# Blue_Pill_Base_Shield.net
KiCad netlist of a schematic drawn in EAGLE
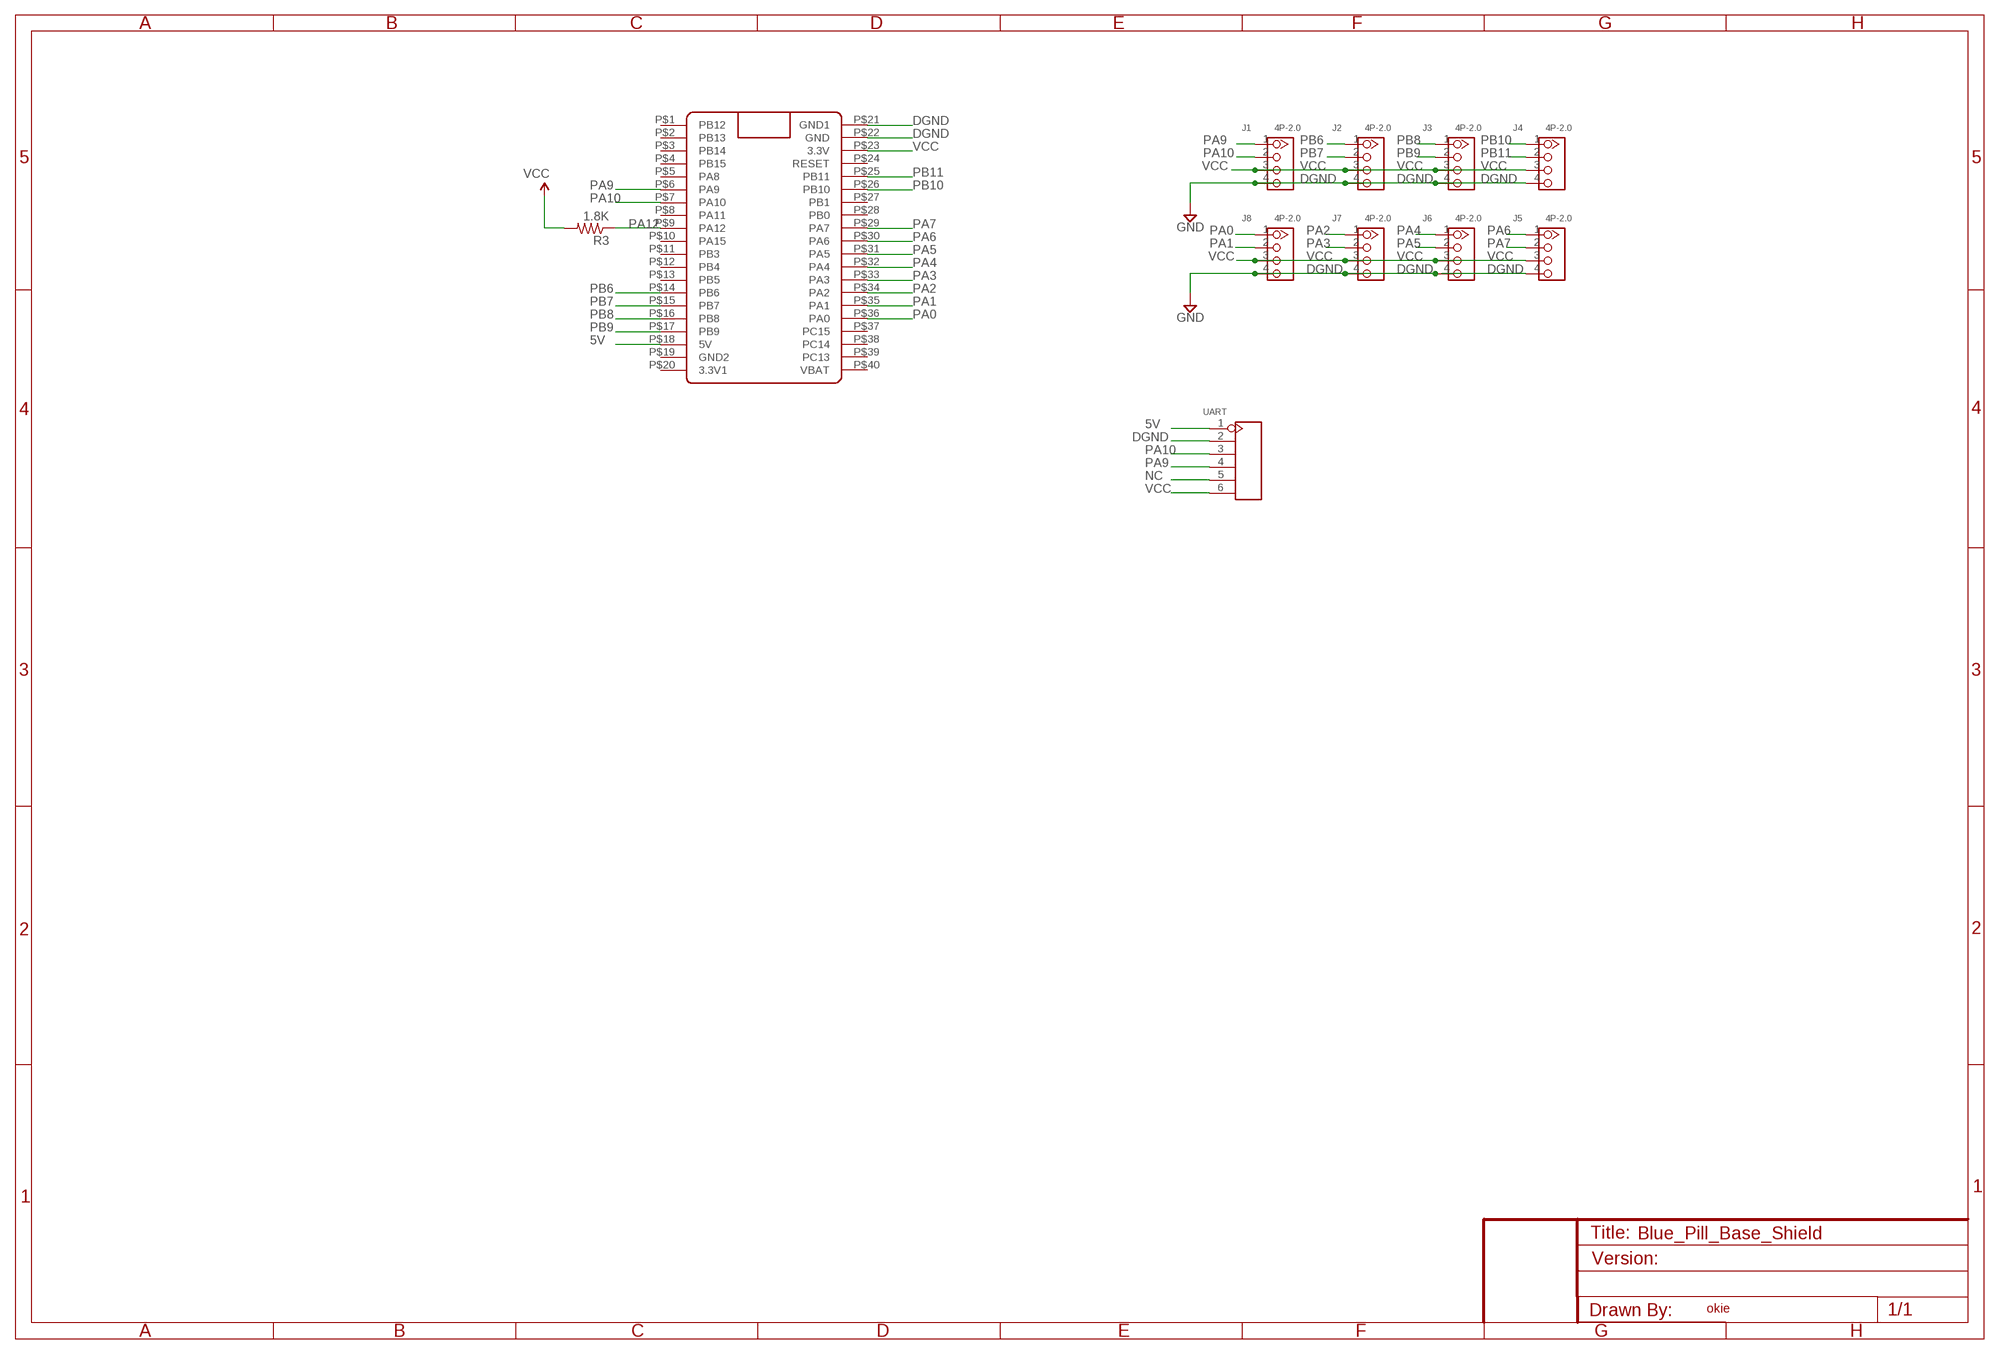
[diagram p0: schematic, sheet 1]

(export (version "E")
  (design (tool "Eeschema 10.0.6"))
  (components
    (comp (ref "J1")
      (value "4P-2.0")
      (footprint "eagle-import:HW4-2.0")
      (libsource (lib "eagle-import") (part "GROVE-CONNECTOR-DIP(4P-2.0)"))
    )
    (comp (ref "J2")
      (value "4P-2.0")
      (footprint "eagle-import:HW4-2.0")
      (libsource (lib "eagle-import") (part "GROVE-CONNECTOR-DIP(4P-2.0)"))
    )
    (comp (ref "J3")
      (value "4P-2.0")
      (footprint "eagle-import:HW4-2.0")
      (libsource (lib "eagle-import") (part "GROVE-CONNECTOR-DIP(4P-2.0)"))
    )
    (comp (ref "J4")
      (value "4P-2.0")
      (footprint "eagle-import:HW4-2.0")
      (libsource (lib "eagle-import") (part "GROVE-CONNECTOR-DIP(4P-2.0)"))
    )
    (comp (ref "J5")
      (value "4P-2.0")
      (footprint "eagle-import:HW4-2.0")
      (libsource (lib "eagle-import") (part "GROVE-CONNECTOR-DIP(4P-2.0)"))
    )
    (comp (ref "J6")
      (value "4P-2.0")
      (footprint "eagle-import:HW4-2.0")
      (libsource (lib "eagle-import") (part "GROVE-CONNECTOR-DIP(4P-2.0)"))
    )
    (comp (ref "J7")
      (value "4P-2.0")
      (footprint "eagle-import:HW4-2.0")
      (libsource (lib "eagle-import") (part "GROVE-CONNECTOR-DIP(4P-2.0)"))
    )
    (comp (ref "J8")
      (value "4P-2.0")
      (footprint "eagle-import:HW4-2.0")
      (libsource (lib "eagle-import") (part "GROVE-CONNECTOR-DIP(4P-2.0)"))
    )
    (comp (ref "R3")
      (value "1.8K")
      (footprint "eagle-import:0603")
      (libsource (lib "eagle-import") (part "RESISTOR0603"))
    )
    (comp (ref "U$5")
      (value "BLUE_PILL")
      (footprint "eagle-import:BLUE_PILL")
      (libsource (lib "eagle-import") (part "BLUE_PILL"))
    )
    (comp (ref "UART")
      (value "YELLOW-6P-2.54")
      (footprint "eagle-import:H6-2.54")
      (fields (field (name "MPN") "F185-1106A1BSYA3"))
      (libsource (lib "eagle-import") (part "DIP-YELLOW-FEMALE-HEADER-VERT(6P-2.54)"))
    )
  )
  (nets
    (net (code "1") (name "/5V") (class "Default")
      (node (ref "U$5") (pin "P$18") (pinfunction "5V_P$18") (pintype "bidirectional"))
      (node (ref "UART") (pin "1") (pinfunction "1_1") (pintype "bidirectional"))
    )
    (net (code "2") (name "/NC") (class "Default")
      (node (ref "UART") (pin "5") (pinfunction "5_5") (pintype "bidirectional"))
    )
    (net (code "3") (name "/PA0") (class "Default")
      (node (ref "J8") (pin "1") (pinfunction "1_1") (pintype "bidirectional"))
      (node (ref "U$5") (pin "P$36") (pinfunction "PA0_P$36") (pintype "bidirectional"))
    )
    (net (code "4") (name "/PA1") (class "Default")
      (node (ref "J8") (pin "2") (pinfunction "2_2") (pintype "bidirectional"))
      (node (ref "U$5") (pin "P$35") (pinfunction "PA1_P$35") (pintype "bidirectional"))
    )
    (net (code "5") (name "/PA2") (class "Default")
      (node (ref "J7") (pin "1") (pinfunction "1_1") (pintype "bidirectional"))
      (node (ref "U$5") (pin "P$34") (pinfunction "PA2_P$34") (pintype "bidirectional"))
    )
    (net (code "6") (name "/PA3") (class "Default")
      (node (ref "J7") (pin "2") (pinfunction "2_2") (pintype "bidirectional"))
      (node (ref "U$5") (pin "P$33") (pinfunction "PA3_P$33") (pintype "bidirectional"))
    )
    (net (code "7") (name "/PA4") (class "Default")
      (node (ref "J6") (pin "1") (pinfunction "1_1") (pintype "bidirectional"))
      (node (ref "U$5") (pin "P$32") (pinfunction "PA4_P$32") (pintype "bidirectional"))
    )
    (net (code "8") (name "/PA5") (class "Default")
      (node (ref "J6") (pin "2") (pinfunction "2_2") (pintype "bidirectional"))
      (node (ref "U$5") (pin "P$31") (pinfunction "PA5_P$31") (pintype "bidirectional"))
    )
    (net (code "9") (name "/PA6") (class "Default")
      (node (ref "J5") (pin "1") (pinfunction "1_1") (pintype "bidirectional"))
      (node (ref "U$5") (pin "P$30") (pinfunction "PA6_P$30") (pintype "bidirectional"))
    )
    (net (code "10") (name "/PA7") (class "Default")
      (node (ref "J5") (pin "2") (pinfunction "2_2") (pintype "bidirectional"))
      (node (ref "U$5") (pin "P$29") (pinfunction "PA7_P$29") (pintype "bidirectional"))
    )
    (net (code "11") (name "/PA9") (class "Default")
      (node (ref "J1") (pin "1") (pinfunction "1_1") (pintype "bidirectional"))
      (node (ref "U$5") (pin "P$6") (pinfunction "PA9_P$6") (pintype "bidirectional"))
      (node (ref "UART") (pin "4") (pinfunction "4_4") (pintype "bidirectional"))
    )
    (net (code "12") (name "/PA10") (class "Default")
      (node (ref "J1") (pin "2") (pinfunction "2_2") (pintype "bidirectional"))
      (node (ref "U$5") (pin "P$7") (pinfunction "PA10_P$7") (pintype "bidirectional"))
      (node (ref "UART") (pin "3") (pinfunction "3_3") (pintype "bidirectional"))
    )
    (net (code "13") (name "/PA12") (class "Default")
      (node (ref "R3") (pin "1") (pinfunction "1_1") (pintype "passive"))
      (node (ref "U$5") (pin "P$9") (pinfunction "PA12_P$9") (pintype "bidirectional"))
    )
    (net (code "14") (name "/PB6") (class "Default")
      (node (ref "J2") (pin "1") (pinfunction "1_1") (pintype "bidirectional"))
      (node (ref "U$5") (pin "P$14") (pinfunction "PB6_P$14") (pintype "bidirectional"))
    )
    (net (code "15") (name "/PB7") (class "Default")
      (node (ref "J2") (pin "2") (pinfunction "2_2") (pintype "bidirectional"))
      (node (ref "U$5") (pin "P$15") (pinfunction "PB7_P$15") (pintype "bidirectional"))
    )
    (net (code "16") (name "/PB8") (class "Default")
      (node (ref "J3") (pin "1") (pinfunction "1_1") (pintype "bidirectional"))
      (node (ref "U$5") (pin "P$16") (pinfunction "PB8_P$16") (pintype "bidirectional"))
    )
    (net (code "17") (name "/PB9") (class "Default")
      (node (ref "J3") (pin "2") (pinfunction "2_2") (pintype "bidirectional"))
      (node (ref "U$5") (pin "P$17") (pinfunction "PB9_P$17") (pintype "bidirectional"))
    )
    (net (code "18") (name "/PB10") (class "Default")
      (node (ref "J4") (pin "1") (pinfunction "1_1") (pintype "bidirectional"))
      (node (ref "U$5") (pin "P$26") (pinfunction "PB10_P$26") (pintype "bidirectional"))
    )
    (net (code "19") (name "/PB11") (class "Default")
      (node (ref "J4") (pin "2") (pinfunction "2_2") (pintype "bidirectional"))
      (node (ref "U$5") (pin "P$25") (pinfunction "PB11_P$25") (pintype "bidirectional"))
    )
    (net (code "20") (name "GND") (class "Default")
      (node (ref "J1") (pin "4") (pinfunction "4_4") (pintype "bidirectional"))
      (node (ref "J2") (pin "4") (pinfunction "4_4") (pintype "bidirectional"))
      (node (ref "J3") (pin "4") (pinfunction "4_4") (pintype "bidirectional"))
      (node (ref "J4") (pin "4") (pinfunction "4_4") (pintype "bidirectional"))
      (node (ref "J5") (pin "4") (pinfunction "4_4") (pintype "bidirectional"))
      (node (ref "J6") (pin "4") (pinfunction "4_4") (pintype "bidirectional"))
      (node (ref "J7") (pin "4") (pinfunction "4_4") (pintype "bidirectional"))
      (node (ref "J8") (pin "4") (pinfunction "4_4") (pintype "bidirectional"))
      (node (ref "U$5") (pin "P$21") (pinfunction "GND1_P$21") (pintype "power_in"))
      (node (ref "U$5") (pin "P$22") (pinfunction "GND_P$22") (pintype "bidirectional"))
      (node (ref "UART") (pin "2") (pinfunction "2_2") (pintype "bidirectional"))
    )
    (net (code "21") (name "VCC") (class "Default")
      (node (ref "J1") (pin "3") (pinfunction "3_3") (pintype "bidirectional"))
      (node (ref "J2") (pin "3") (pinfunction "3_3") (pintype "bidirectional"))
      (node (ref "J3") (pin "3") (pinfunction "3_3") (pintype "bidirectional"))
      (node (ref "J4") (pin "3") (pinfunction "3_3") (pintype "bidirectional"))
      (node (ref "J5") (pin "3") (pinfunction "3_3") (pintype "bidirectional"))
      (node (ref "J6") (pin "3") (pinfunction "3_3") (pintype "bidirectional"))
      (node (ref "J7") (pin "3") (pinfunction "3_3") (pintype "bidirectional"))
      (node (ref "J8") (pin "3") (pinfunction "3_3") (pintype "bidirectional"))
      (node (ref "R3") (pin "2") (pinfunction "2_2") (pintype "passive"))
      (node (ref "U$5") (pin "P$23") (pinfunction "3.3V_P$23") (pintype "bidirectional"))
      (node (ref "UART") (pin "6") (pinfunction "6_6") (pintype "bidirectional"))
    )
    (net (code "22") (name "unconnected-(U$5-3.3V1-PadP$20)") (class "Default")
      (node (ref "U$5") (pin "P$20") (pinfunction "3.3V1_P$20") (pintype "bidirectional"))
    )
    (net (code "23") (name "unconnected-(U$5-GND2-PadP$19)") (class "Default")
      (node (ref "U$5") (pin "P$19") (pinfunction "GND2_P$19") (pintype "bidirectional"))
    )
    (net (code "24") (name "unconnected-(U$5-PA8-PadP$5)") (class "Default")
      (node (ref "U$5") (pin "P$5") (pinfunction "PA8_P$5") (pintype "bidirectional"))
    )
    (net (code "25") (name "unconnected-(U$5-PA11-PadP$8)") (class "Default")
      (node (ref "U$5") (pin "P$8") (pinfunction "PA11_P$8") (pintype "bidirectional"))
    )
    (net (code "26") (name "unconnected-(U$5-PA15-PadP$10)") (class "Default")
      (node (ref "U$5") (pin "P$10") (pinfunction "PA15_P$10") (pintype "bidirectional"))
    )
    (net (code "27") (name "unconnected-(U$5-PB0-PadP$28)") (class "Default")
      (node (ref "U$5") (pin "P$28") (pinfunction "PB0_P$28") (pintype "bidirectional"))
    )
    (net (code "28") (name "unconnected-(U$5-PB1-PadP$27)") (class "Default")
      (node (ref "U$5") (pin "P$27") (pinfunction "PB1_P$27") (pintype "bidirectional"))
    )
    (net (code "29") (name "unconnected-(U$5-PB3-PadP$11)") (class "Default")
      (node (ref "U$5") (pin "P$11") (pinfunction "PB3_P$11") (pintype "bidirectional"))
    )
    (net (code "30") (name "unconnected-(U$5-PB4-PadP$12)") (class "Default")
      (node (ref "U$5") (pin "P$12") (pinfunction "PB4_P$12") (pintype "bidirectional"))
    )
    (net (code "31") (name "unconnected-(U$5-PB5-PadP$13)") (class "Default")
      (node (ref "U$5") (pin "P$13") (pinfunction "PB5_P$13") (pintype "bidirectional"))
    )
    (net (code "32") (name "unconnected-(U$5-PB12-PadP$1)") (class "Default")
      (node (ref "U$5") (pin "P$1") (pinfunction "PB12_P$1") (pintype "bidirectional"))
    )
    (net (code "33") (name "unconnected-(U$5-PB13-PadP$2)") (class "Default")
      (node (ref "U$5") (pin "P$2") (pinfunction "PB13_P$2") (pintype "bidirectional"))
    )
    (net (code "34") (name "unconnected-(U$5-PB14-PadP$3)") (class "Default")
      (node (ref "U$5") (pin "P$3") (pinfunction "PB14_P$3") (pintype "bidirectional"))
    )
    (net (code "35") (name "unconnected-(U$5-PB15-PadP$4)") (class "Default")
      (node (ref "U$5") (pin "P$4") (pinfunction "PB15_P$4") (pintype "bidirectional"))
    )
    (net (code "36") (name "unconnected-(U$5-PC13-PadP$39)") (class "Default")
      (node (ref "U$5") (pin "P$39") (pinfunction "PC13_P$39") (pintype "bidirectional"))
    )
    (net (code "37") (name "unconnected-(U$5-PC14-PadP$38)") (class "Default")
      (node (ref "U$5") (pin "P$38") (pinfunction "PC14_P$38") (pintype "bidirectional"))
    )
    (net (code "38") (name "unconnected-(U$5-PC15-PadP$37)") (class "Default")
      (node (ref "U$5") (pin "P$37") (pinfunction "PC15_P$37") (pintype "bidirectional"))
    )
    (net (code "39") (name "unconnected-(U$5-RESET-PadP$24)") (class "Default")
      (node (ref "U$5") (pin "P$24") (pinfunction "RESET_P$24") (pintype "bidirectional"))
    )
    (net (code "40") (name "unconnected-(U$5-VBAT-PadP$40)") (class "Default")
      (node (ref "U$5") (pin "P$40") (pinfunction "VBAT_P$40") (pintype "bidirectional"))
    )
  )
)
